# PowerSupply.net
KiCad netlist of a schematic drawn in Altium Designer
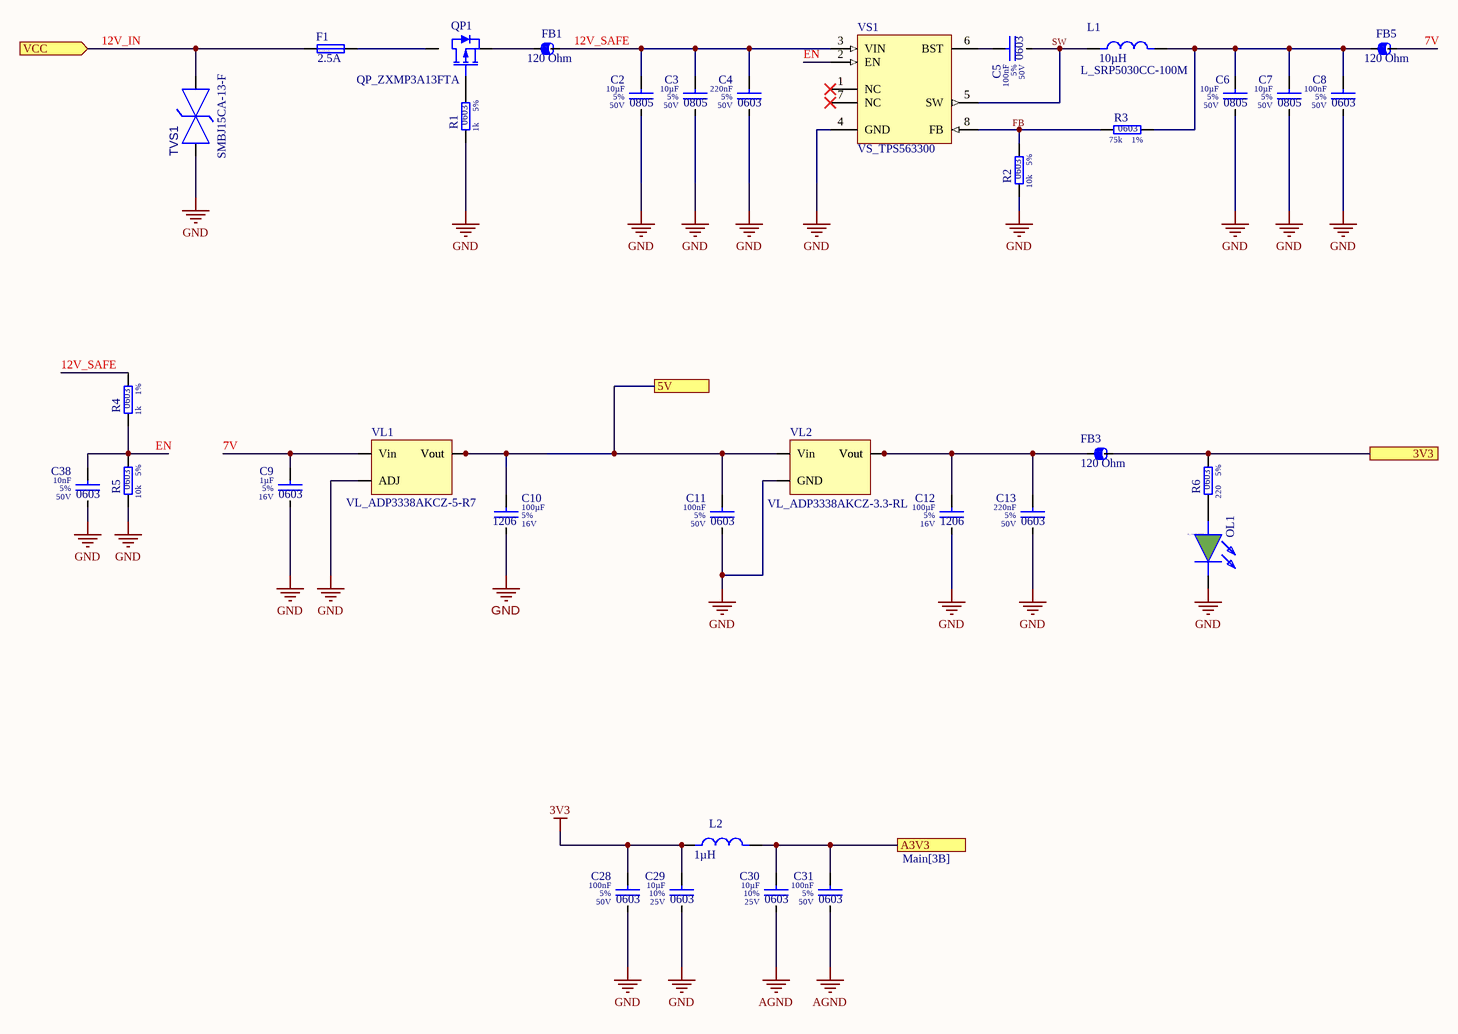
[diagram p0: PowerSupply.SchDoc]

(export (version "E")
  (design (tool "Eeschema 10.0.6"))
  (components
    (comp (ref "C2")
      (value "10µF")
      (footprint "0805_Capacitor")
      (description "C_10u_50V_0805_10")
      (fields
        (field (name "TOLERANCE") "5%")
        (field (name "VOLTAGE RATING") "50V")
        (field (name "CASE/PACKAGE") "0805")
      )
      (libsource (lib "Altium Concord Pro on A365") (part "Capacitor"))
    )
    (comp (ref "C3")
      (value "10µF")
      (footprint "0805_Capacitor")
      (description "C_10u_50V_0805_10")
      (fields
        (field (name "TOLERANCE") "5%")
        (field (name "VOLTAGE RATING") "50V")
        (field (name "CASE/PACKAGE") "0805")
      )
      (libsource (lib "Altium Concord Pro on A365") (part "Capacitor"))
    )
    (comp (ref "C4")
      (value "220nF")
      (footprint "0603_HandSold_Capacitor")
      (description "C_220n_50V_0603_5")
      (fields
        (field (name "TOLERANCE") "5%")
        (field (name "VOLTAGE RATING") "50V")
        (field (name "CASE/PACKAGE") "0603")
      )
      (libsource (lib "Altium Concord Pro on A365") (part "Capacitor"))
    )
    (comp (ref "C5")
      (value "100nF")
      (footprint "0603_HandSold_Capacitor")
      (description "C_100n_50V_0603_5")
      (fields
        (field (name "TOLERANCE") "5%")
        (field (name "VOLTAGE RATING") "50V")
        (field (name "CASE/PACKAGE") "0603")
      )
      (libsource (lib "Altium Concord Pro on A365") (part "Capacitor"))
    )
    (comp (ref "C6")
      (value "10µF")
      (footprint "0805_Capacitor")
      (description "C_10u_50V_0805_10")
      (fields
        (field (name "TOLERANCE") "5%")
        (field (name "VOLTAGE RATING") "50V")
        (field (name "CASE/PACKAGE") "0805")
      )
      (libsource (lib "Altium Concord Pro on A365") (part "Capacitor"))
    )
    (comp (ref "C7")
      (value "10µF")
      (footprint "0805_Capacitor")
      (description "C_10u_50V_0805_10")
      (fields
        (field (name "TOLERANCE") "5%")
        (field (name "VOLTAGE RATING") "50V")
        (field (name "CASE/PACKAGE") "0805")
      )
      (libsource (lib "Altium Concord Pro on A365") (part "Capacitor"))
    )
    (comp (ref "C8")
      (value "100nF")
      (footprint "0603_HandSold_Capacitor")
      (description "C_100n_50V_0603_5")
      (fields
        (field (name "TOLERANCE") "5%")
        (field (name "VOLTAGE RATING") "50V")
        (field (name "CASE/PACKAGE") "0603")
      )
      (libsource (lib "Altium Concord Pro on A365") (part "Capacitor"))
    )
    (comp (ref "C9")
      (value "1µF")
      (footprint "0603_HandSold_Capacitor")
      (description "C_1u_16V_0603_5")
      (fields
        (field (name "TOLERANCE") "5%")
        (field (name "VOLTAGE RATING") "16V")
        (field (name "CASE/PACKAGE") "0603")
      )
      (libsource (lib "Altium Concord Pro on A365") (part "Capacitor"))
    )
    (comp (ref "C10")
      (value "100µF")
      (footprint "1206_HandSold_Capacitor")
      (description "C_100u_16V_1206_5")
      (fields
        (field (name "TOLERANCE") "5%")
        (field (name "VOLTAGE RATING") "16V")
        (field (name "CASE/PACKAGE") "1206")
      )
      (libsource (lib "Altium Concord Pro on A365") (part "Capacitor"))
    )
    (comp (ref "C11")
      (value "100nF")
      (footprint "0603_HandSold_Capacitor")
      (description "C_100n_50V_0603_5")
      (fields
        (field (name "TOLERANCE") "5%")
        (field (name "VOLTAGE RATING") "50V")
        (field (name "CASE/PACKAGE") "0603")
      )
      (libsource (lib "Altium Concord Pro on A365") (part "Capacitor"))
    )
    (comp (ref "C12")
      (value "100µF")
      (footprint "1206_HandSold_Capacitor")
      (description "C_100u_16V_1206_5")
      (fields
        (field (name "TOLERANCE") "5%")
        (field (name "VOLTAGE RATING") "16V")
        (field (name "CASE/PACKAGE") "1206")
      )
      (libsource (lib "Altium Concord Pro on A365") (part "Capacitor"))
    )
    (comp (ref "C13")
      (value "220nF")
      (footprint "0603_HandSold_Capacitor")
      (description "C_220n_50V_0603_5")
      (fields
        (field (name "TOLERANCE") "5%")
        (field (name "VOLTAGE RATING") "50V")
        (field (name "CASE/PACKAGE") "0603")
      )
      (libsource (lib "Altium Concord Pro on A365") (part "Capacitor"))
    )
    (comp (ref "C28")
      (value "100nF")
      (footprint "0603_HandSold_Capacitor")
      (description "C_100n_50V_0603_5")
      (fields
        (field (name "TOLERANCE") "5%")
        (field (name "VOLTAGE RATING") "50V")
        (field (name "CASE/PACKAGE") "0603")
      )
      (libsource (lib "Altium Concord Pro on A365") (part "Capacitor"))
    )
    (comp (ref "C29")
      (value "10µF")
      (footprint "0603_HandSold_Capacitor")
      (description "C_10u_10V_0603_10")
      (fields
        (field (name "TOLERANCE") "10%")
        (field (name "VOLTAGE RATING") "25V")
        (field (name "CASE/PACKAGE") "0603")
        (field (name "Comment") "C_10u_25V_0603_10")
      )
      (libsource (lib "Altium Concord Pro on A365") (part "Capacitor"))
    )
    (comp (ref "C30")
      (value "10µF")
      (footprint "0603_HandSold_Capacitor")
      (description "C_10u_10V_0603_10")
      (fields
        (field (name "TOLERANCE") "10%")
        (field (name "VOLTAGE RATING") "25V")
        (field (name "CASE/PACKAGE") "0603")
        (field (name "Comment") "C_10u_25V_0603_10")
      )
      (libsource (lib "Altium Concord Pro on A365") (part "Capacitor"))
    )
    (comp (ref "C31")
      (value "100nF")
      (footprint "0603_HandSold_Capacitor")
      (description "C_100n_50V_0603_5")
      (fields
        (field (name "TOLERANCE") "5%")
        (field (name "VOLTAGE RATING") "50V")
        (field (name "CASE/PACKAGE") "0603")
      )
      (libsource (lib "Altium Concord Pro on A365") (part "Capacitor"))
    )
    (comp (ref "C38")
      (value "10nF")
      (footprint "0603_HandSold_Capacitor")
      (description "C_10n_50V_0603_5")
      (fields
        (field (name "TOLERANCE") "5%")
        (field (name "VOLTAGE RATING") "50V")
        (field (name "CASE/PACKAGE") "0603")
      )
      (libsource (lib "Altium Concord Pro on A365") (part "Capacitor"))
    )
    (comp (ref "F1")
      (value "F_1210_2.5A")
      (footprint "1210")
      (description "Fuse; Resettable; MF-USHT; 0.5A, 2.5A, 20A; 30V, smt")
      (fields (field (name "TRIP CURRENT") "2.5A"))
      (libsource (lib "Altium Concord Pro on A365") (part "Fuse"))
    )
    (comp (ref "FB1")
      (value "FB_BLM21PG121SN1D")
      (footprint "0805_FB")
      (description "Ferrite Beads 120 OHM 25% Alternate Sizing Guide Below")
      (fields (field (name "IMPEDANCE") "120 Ohm"))
      (libsource (lib "Altium Concord Pro on A365") (part "FerriteBead"))
    )
    (comp (ref "FB3")
      (value "FB_BLM21PG121SN1D")
      (footprint "0805_FB")
      (description "Ferrite Beads 120 OHM 25% Alternate Sizing Guide Below")
      (fields (field (name "IMPEDANCE") "120 Ohm"))
      (libsource (lib "Altium Concord Pro on A365") (part "FerriteBead"))
    )
    (comp (ref "FB5")
      (value "FB_BLM21PG121SN1D")
      (footprint "0805_FB")
      (description "Ferrite Beads 120 OHM 25% Alternate Sizing Guide Below")
      (fields (field (name "IMPEDANCE") "120 Ohm"))
      (libsource (lib "Altium Concord Pro on A365") (part "FerriteBead"))
    )
    (comp (ref "L1")
      (value "L_SRP5030CC-100M")
      (footprint "L_2220")
      (description "SMD Ind,5.7x5.2x2.8mm,10uH+/-20%,2.8A,shd")
      (fields (field (name "ALTIUM_VALUE") "10µH"))
      (libsource (lib "Altium Concord Pro on A365") (part "Inductor"))
    )
    (comp (ref "L2")
      (value "1µH")
      (footprint "0805_HandSold_Inductor")
      (description "Inductor; 1uH, 3.1A, 60mΩ, 20%, SMT")
      (fields (field (name "TOLERANCE") "20%") (field (name "Comment") "L_TMS201610ALM-1R0MTAA"))
      (libsource (lib "Altium Concord Pro on A365") (part "ASPI-8040S-750M-T"))
    )
    (comp (ref "OL1")
      (value "OL_150060VS75000")
      (footprint "0603_HandSold_LED")
      (description "LED, 0603 Green 2V 30mA  72mW")
      (fields (field (name "POWER") "72mW"))
      (libsource (lib "Altium Concord Pro on A365") (part "OL_GREEN"))
    )
    (comp (ref "QP1")
      (value "QP_ZXMP3A13FTA")
      (footprint "SOT23")
      (description "MOSFET 30V P-Chnl UMOS")
      (fields (field (name "POWER") "625mW"))
      (libsource (lib "Altium Concord Pro on A365") (part "PMOS"))
    )
    (comp (ref "R1")
      (value "R_1k_0603_5")
      (footprint "0603_HandSold_Resistor")
      (fields
        (field (name "TOLERANCE") "5%")
        (field (name "RESISTANCE") "1k")
        (field (name "CASE/PACKAGE") "0603")
        (field (name "POWER") "100mW")
      )
      (libsource (lib "Altium Concord Pro on A365") (part "Resistor"))
    )
    (comp (ref "R2")
      (value "R_10k_0603_5")
      (footprint "0603_HandSold_Resistor")
      (fields
        (field (name "TOLERANCE") "5%")
        (field (name "RESISTANCE") "10k")
        (field (name "CASE/PACKAGE") "0603")
        (field (name "POWER") "100mW")
      )
      (libsource (lib "Altium Concord Pro on A365") (part "Resistor"))
    )
    (comp (ref "R3")
      (value "R_75k_0603_1")
      (footprint "0603_HandSold_Resistor")
      (fields
        (field (name "TOLERANCE") "1%")
        (field (name "RESISTANCE") "75k")
        (field (name "CASE/PACKAGE") "0603")
        (field (name "POWER") "100mW")
      )
      (libsource (lib "Altium Concord Pro on A365") (part "Resistor"))
    )
    (comp (ref "R4")
      (value "R_27k_0603_1")
      (footprint "0603_HandSold_Resistor")
      (fields
        (field (name "TOLERANCE") "1%")
        (field (name "RESISTANCE") "1k")
        (field (name "CASE/PACKAGE") "0603")
        (field (name "POWER") "100mW")
      )
      (libsource (lib "Altium Concord Pro on A365") (part "Resistor"))
    )
    (comp (ref "R5")
      (value "R_10k_0603_5")
      (footprint "0603_HandSold_Resistor")
      (fields
        (field (name "TOLERANCE") "5%")
        (field (name "RESISTANCE") "10k")
        (field (name "CASE/PACKAGE") "0603")
        (field (name "POWER") "100mW")
      )
      (libsource (lib "Altium Concord Pro on A365") (part "Resistor"))
    )
    (comp (ref "R6")
      (value "R_220_0603_5")
      (footprint "0603_HandSold_Resistor")
      (fields
        (field (name "TOLERANCE") "5%")
        (field (name "RESISTANCE") "220")
        (field (name "CASE/PACKAGE") "0603")
        (field (name "POWER") "100mW")
      )
      (libsource (lib "Altium Concord Pro on A365") (part "Resistor"))
    )
    (comp (ref "TVS1")
      (value "TVS_SMBJ15CA-13-F")
      (footprint "DO-214AA (SMB J-Bend) footprint")
      (description "Diode; TVS; Bidirectional; 15V, 16.7V, 24.4V SMT")
      (fields (field (name "MAN. PART NUM.") "SMBJ15CA-13-F"))
      (libsource (lib "Altium Concord Pro on A365") (part "TVS Bidirectional"))
    )
    (comp (ref "VL1")
      (value "VL_ADP3338AKCZ-5-R7")
      (footprint "SOT223-3")
      (description "LDO; ADP3338AKCZ-5-R7; 1A; 5V; High accuracy over line and load: ±0.8% @ 25°C,")
      (fields (field (name "POWER") "5W"))
      (libsource (lib "Altium Concord Pro on A365") (part "LD1117 Series Adjustable"))
    )
    (comp (ref "VL2")
      (value "VL_ADP3338AKCZ-3.3-RL")
      (footprint "SOT223-3")
      (description "LDO; ADP3338AKCZ-5-R7; 1A; 3.3V; High accuracy over line and load: ±0.8% @ 25°C,")
      (fields (field (name "POWER") "5W"))
      (libsource (lib "") (part "LD1117 Series Adjustable_1"))
    )
    (comp (ref "VS1")
      (value "VS_TPS563300")
      (footprint "SOT-5X3-8")
      (description "DC/DC Buck; 3.8-V to 28-V, 3-A Synchronous Buck Converter in SOT583 Package")
      (libsource (lib "Altium Concord Pro on A365") (part "VS_TPS563300"))
    )
  )
  (nets
    (net (code "1") (name "/5V") (class "Default")
      (node (ref "C10") (pin "1") (pinfunction "1_1") (pintype "passive"))
      (node (ref "C11") (pin "1") (pinfunction "1_1") (pintype "passive"))
      (node (ref "VL1") (pin "2") (pinfunction "Vout_2") (pintype "passive"))
      (node (ref "VL1") (pin "4") (pinfunction "Vout_4") (pintype "passive"))
      (node (ref "VL2") (pin "3") (pinfunction "Vin_3") (pintype "passive"))
    )
    (net (code "2") (name "/7V") (class "Default")
      (node (ref "C9") (pin "1") (pinfunction "1_1") (pintype "passive"))
      (node (ref "FB5") (pin "2") (pinfunction "2_2") (pintype "passive"))
      (node (ref "VL1") (pin "3") (pinfunction "Vin_3") (pintype "passive"))
    )
    (net (code "3") (name "/12V_IN") (class "Default")
      (node (ref "F1") (pin "1") (pinfunction "1_1") (pintype "passive"))
      (node (ref "TVS1") (pin "2") (pinfunction "2_2") (pintype "passive"))
    )
    (net (code "4") (name "/12V_SAFE") (class "Default")
      (node (ref "C2") (pin "1") (pinfunction "1_1") (pintype "passive"))
      (node (ref "C3") (pin "1") (pinfunction "1_1") (pintype "passive"))
      (node (ref "C4") (pin "1") (pinfunction "1_1") (pintype "passive"))
      (node (ref "FB1") (pin "2") (pinfunction "2_2") (pintype "passive"))
      (node (ref "R4") (pin "2") (pinfunction "2_2") (pintype "passive"))
      (node (ref "VS1") (pin "3") (pinfunction "VIN_3") (pintype "input"))
    )
    (net (code "5") (name "/A3V3") (class "Default")
      (node (ref "C30") (pin "1") (pinfunction "1_1") (pintype "passive"))
      (node (ref "C31") (pin "1") (pinfunction "1_1") (pintype "passive"))
      (node (ref "L2") (pin "2") (pinfunction "2_2") (pintype "passive"))
    )
    (net (code "6") (name "/EN") (class "Default")
      (node (ref "C38") (pin "1") (pinfunction "1_1") (pintype "passive"))
      (node (ref "R4") (pin "1") (pinfunction "1_1") (pintype "passive"))
      (node (ref "R5") (pin "2") (pinfunction "2_2") (pintype "passive"))
      (node (ref "VS1") (pin "2") (pinfunction "EN_2") (pintype "input"))
    )
    (net (code "7") (name "/FB") (class "Default")
      (node (ref "R2") (pin "2") (pinfunction "2_2") (pintype "passive"))
      (node (ref "R3") (pin "1") (pinfunction "1_1") (pintype "passive"))
      (node (ref "VS1") (pin "8") (pinfunction "FB_8") (pintype "input"))
    )
    (net (code "8") (name "/SW") (class "Default")
      (node (ref "C5") (pin "2") (pinfunction "2_2") (pintype "passive"))
      (node (ref "L1") (pin "1") (pinfunction "1_1") (pintype "passive"))
      (node (ref "VS1") (pin "5") (pinfunction "SW_5") (pintype "output"))
    )
    (net (code "9") (name "3V3") (class "Default")
      (node (ref "C28") (pin "1") (pinfunction "1_1") (pintype "passive"))
      (node (ref "C29") (pin "1") (pinfunction "1_1") (pintype "passive"))
      (node (ref "FB3") (pin "2") (pinfunction "2_2") (pintype "passive"))
      (node (ref "L2") (pin "1") (pinfunction "1_1") (pintype "passive"))
      (node (ref "R6") (pin "2") (pinfunction "2_2") (pintype "passive"))
    )
    (net (code "10") (name "AGND") (class "Default")
      (node (ref "C30") (pin "2") (pinfunction "2_2") (pintype "passive"))
      (node (ref "C31") (pin "2") (pinfunction "2_2") (pintype "passive"))
    )
    (net (code "11") (name "GND") (class "Default")
      (node (ref "C10") (pin "2") (pinfunction "2_2") (pintype "passive"))
      (node (ref "C11") (pin "2") (pinfunction "2_2") (pintype "passive"))
      (node (ref "C12") (pin "2") (pinfunction "2_2") (pintype "passive"))
      (node (ref "C13") (pin "2") (pinfunction "2_2") (pintype "passive"))
      (node (ref "C2") (pin "2") (pinfunction "2_2") (pintype "passive"))
      (node (ref "C28") (pin "2") (pinfunction "2_2") (pintype "passive"))
      (node (ref "C29") (pin "2") (pinfunction "2_2") (pintype "passive"))
      (node (ref "C3") (pin "2") (pinfunction "2_2") (pintype "passive"))
      (node (ref "C38") (pin "2") (pinfunction "2_2") (pintype "passive"))
      (node (ref "C4") (pin "2") (pinfunction "2_2") (pintype "passive"))
      (node (ref "C6") (pin "2") (pinfunction "2_2") (pintype "passive"))
      (node (ref "C7") (pin "2") (pinfunction "2_2") (pintype "passive"))
      (node (ref "C8") (pin "2") (pinfunction "2_2") (pintype "passive"))
      (node (ref "C9") (pin "2") (pinfunction "2_2") (pintype "passive"))
      (node (ref "OL1") (pin "1") (pinfunction "K_1") (pintype "passive"))
      (node (ref "R1") (pin "1") (pinfunction "1_1") (pintype "passive"))
      (node (ref "R2") (pin "1") (pinfunction "1_1") (pintype "passive"))
      (node (ref "R5") (pin "1") (pinfunction "1_1") (pintype "passive"))
      (node (ref "TVS1") (pin "1") (pinfunction "1_1") (pintype "passive"))
      (node (ref "VL1") (pin "1") (pinfunction "ADJ_1") (pintype "passive"))
      (node (ref "VL2") (pin "1") (pinfunction "GND_1") (pintype "passive"))
      (node (ref "VS1") (pin "4") (pinfunction "GND_4") (pintype "power_in"))
    )
    (net (code "12") (name "Net-(C6-Pad1)") (class "Default")
      (node (ref "C6") (pin "1") (pinfunction "1_1") (pintype "passive"))
      (node (ref "C7") (pin "1") (pinfunction "1_1") (pintype "passive"))
      (node (ref "C8") (pin "1") (pinfunction "1_1") (pintype "passive"))
      (node (ref "FB5") (pin "1") (pinfunction "1_1") (pintype "passive"))
      (node (ref "L1") (pin "2") (pinfunction "2_2") (pintype "passive"))
      (node (ref "R3") (pin "2") (pinfunction "2_2") (pintype "passive"))
    )
    (net (code "13") (name "Net-(C12-Pad1)") (class "Default")
      (node (ref "C12") (pin "1") (pinfunction "1_1") (pintype "passive"))
      (node (ref "C13") (pin "1") (pinfunction "1_1") (pintype "passive"))
      (node (ref "FB3") (pin "1") (pinfunction "1_1") (pintype "passive"))
      (node (ref "VL2") (pin "2") (pinfunction "Vout_2") (pintype "passive"))
      (node (ref "VL2") (pin "4") (pinfunction "Vout_4") (pintype "passive"))
    )
    (net (code "14") (name "Net-(OL1-A)") (class "Default")
      (node (ref "OL1") (pin "2") (pinfunction "A_2") (pintype "passive"))
      (node (ref "R6") (pin "1") (pinfunction "1_1") (pintype "passive"))
    )
    (net (code "15") (name "Net-(QP1-D)") (class "Default")
      (node (ref "F1") (pin "2") (pinfunction "2_2") (pintype "passive"))
      (node (ref "QP1") (pin "3") (pinfunction "D_3") (pintype "passive"))
    )
    (net (code "16") (name "Net-(QP1-G)") (class "Default")
      (node (ref "QP1") (pin "1") (pinfunction "G_1") (pintype "passive"))
      (node (ref "R1") (pin "2") (pinfunction "2_2") (pintype "passive"))
    )
    (net (code "17") (name "Net-(QP1-S)") (class "Default")
      (node (ref "FB1") (pin "1") (pinfunction "1_1") (pintype "passive"))
      (node (ref "QP1") (pin "2") (pinfunction "S_2") (pintype "passive"))
    )
    (net (code "18") (name "Net-(VS1-BST)") (class "Default")
      (node (ref "C5") (pin "1") (pinfunction "1_1") (pintype "passive"))
      (node (ref "VS1") (pin "6") (pinfunction "BST_6") (pintype "passive"))
    )
    (net (code "19") (name "unconnected-(VS1-NC-Pad1)") (class "Default")
      (node (ref "VS1") (pin "1") (pinfunction "NC_1") (pintype "passive+no_connect"))
    )
    (net (code "20") (name "unconnected-(VS1-NC-Pad7)") (class "Default")
      (node (ref "VS1") (pin "7") (pinfunction "NC_7") (pintype "passive+no_connect"))
    )
  )
)
